# TPS54331_Neko_BEC.net
KiCad netlist of a schematic drawn in EasyEDA Pro
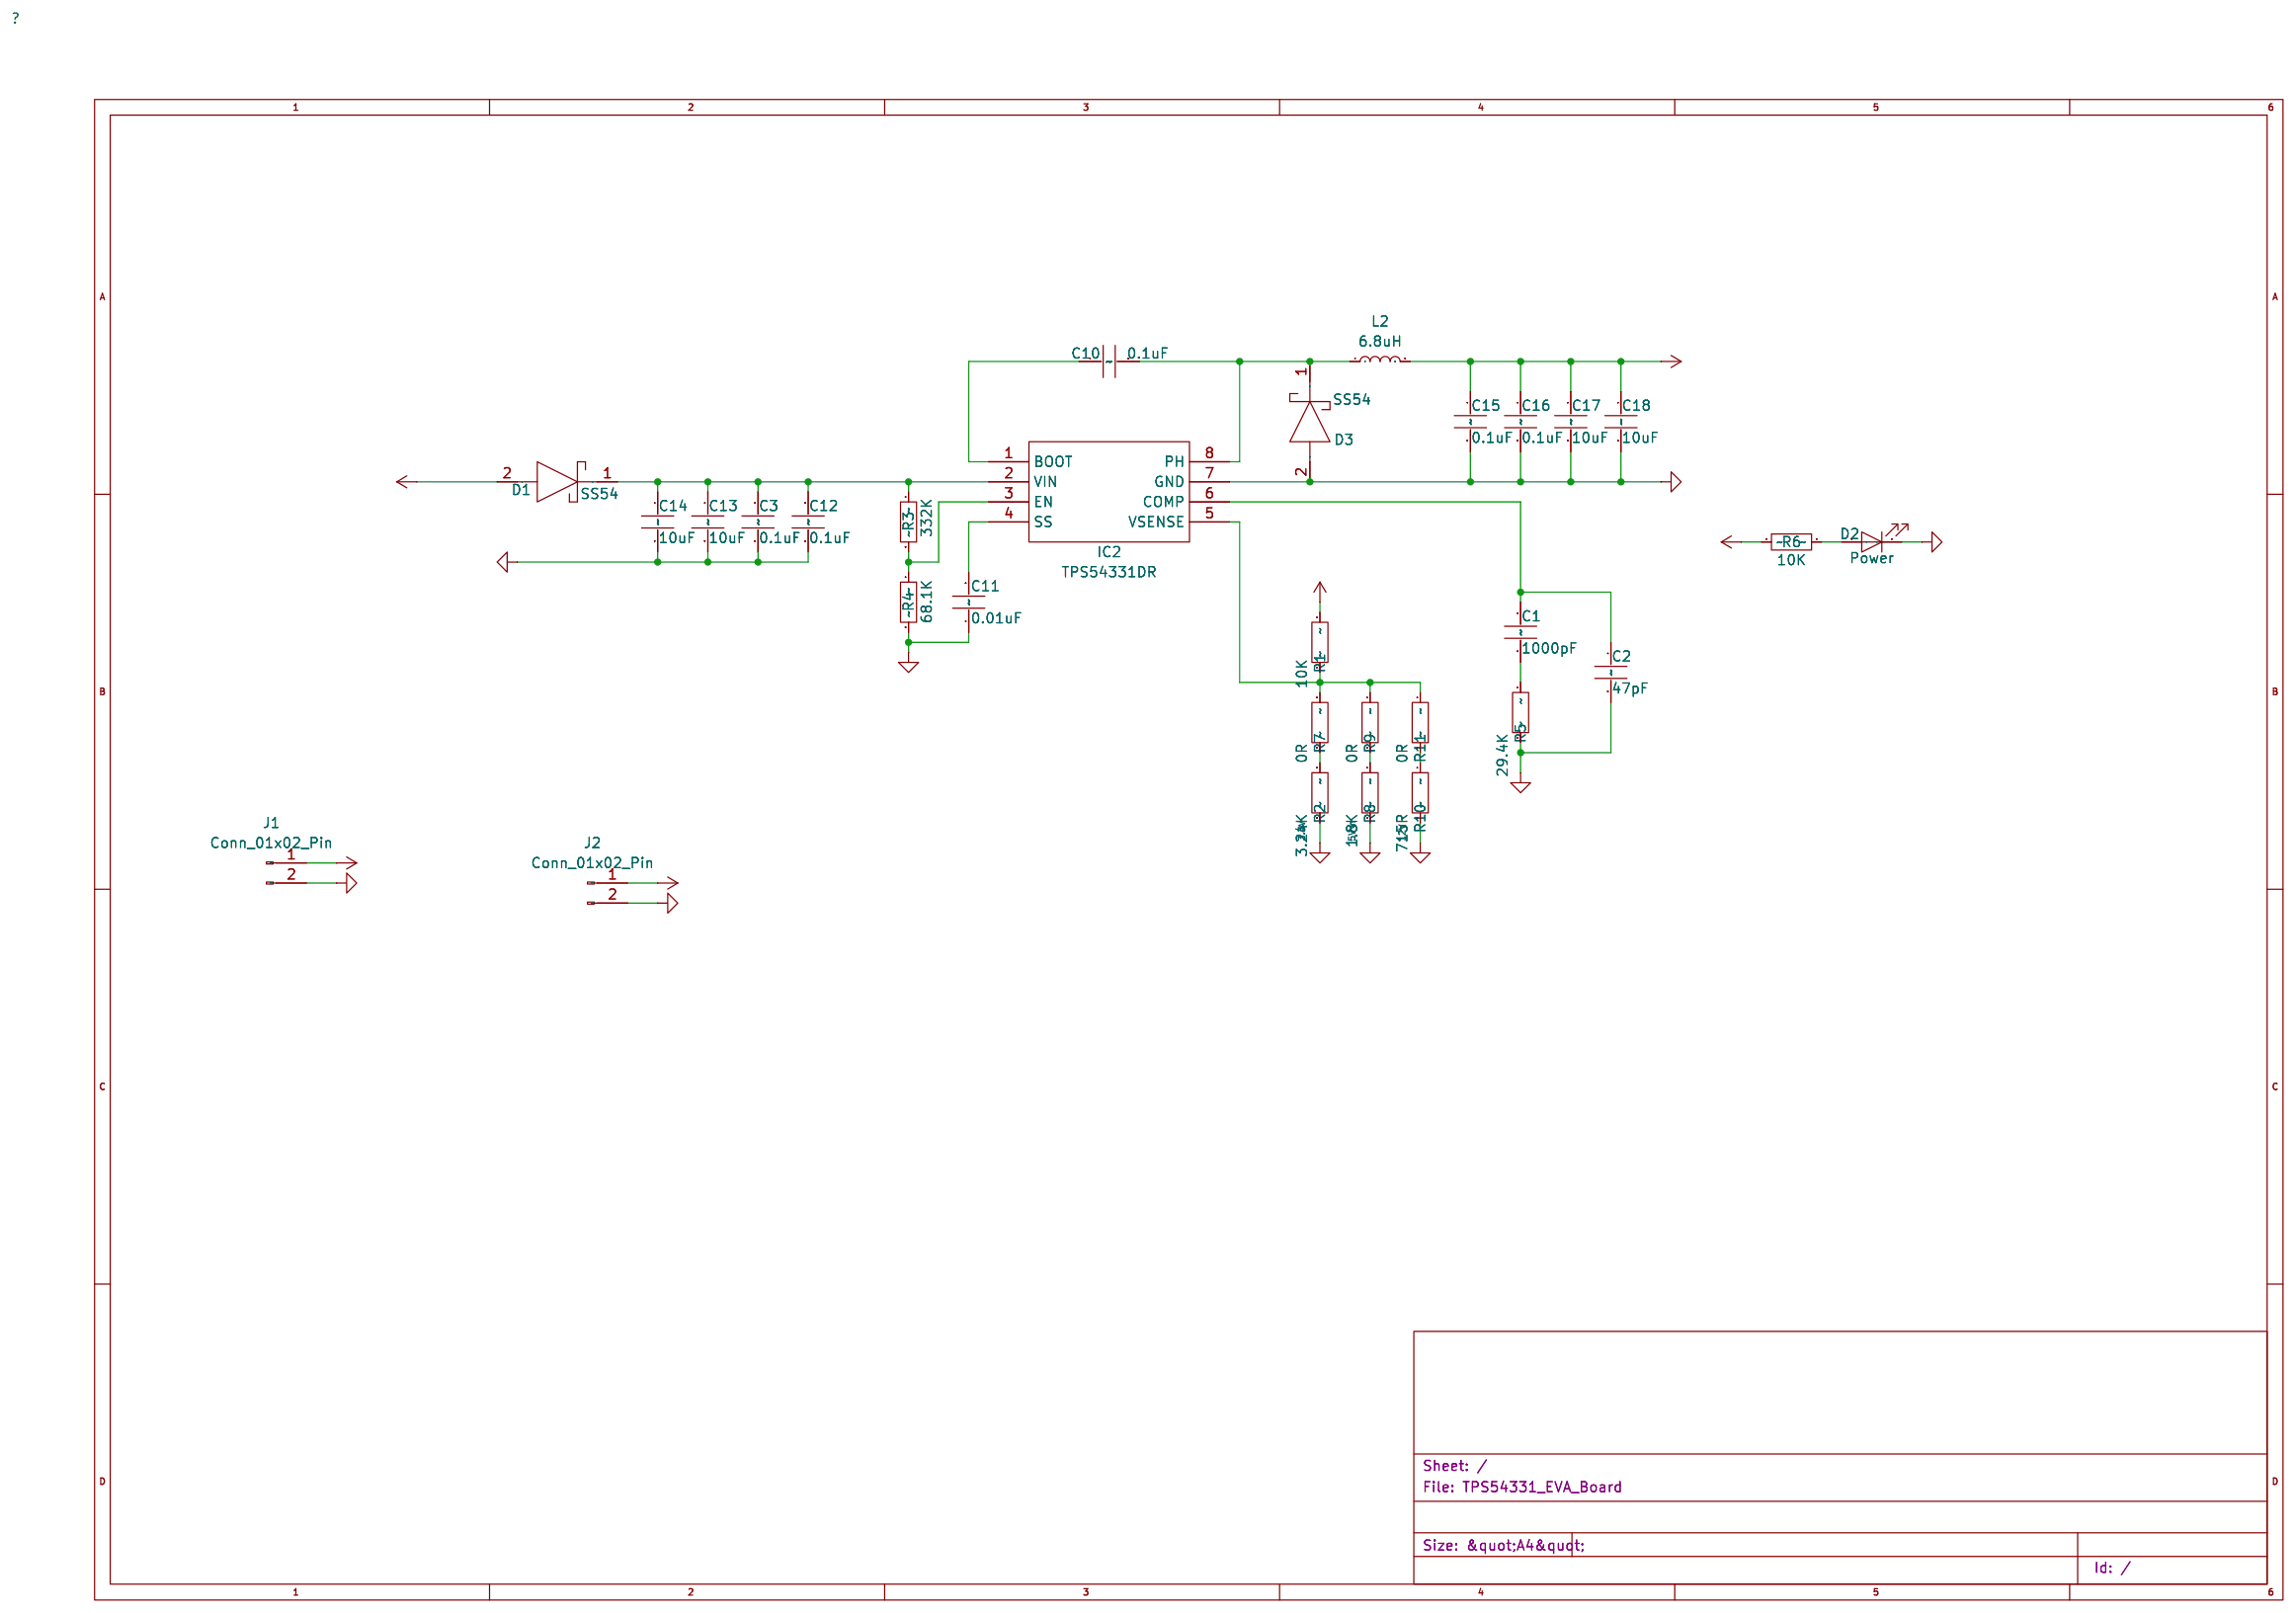
[diagram p0: schematic sheet]

(export (version "E")
  (design (tool "Eeschema 10.0.6"))
  (components
    (comp (ref "C1")
      (value "1000pF")
      (footprint "easyedapro:Capacitor_SMD:C_1206_3216Metric")
      (description "Unpolarized capacitor")
      (libsource (lib "easyedapro") (part "Device_C"))
    )
    (comp (ref "C2")
      (value "47pF")
      (footprint "easyedapro:Capacitor_SMD:C_1206_3216Metric")
      (description "Unpolarized capacitor")
      (libsource (lib "easyedapro") (part "Device_C"))
    )
    (comp (ref "C3")
      (value "0.1uF")
      (footprint "easyedapro:Capacitor_SMD:C_1206_3216Metric")
      (description "Unpolarized capacitor")
      (libsource (lib "easyedapro") (part "Device_C"))
    )
    (comp (ref "C10")
      (value "0.1uF")
      (footprint "easyedapro:Capacitor_SMD:C_1206_3216Metric")
      (description "Unpolarized capacitor")
      (libsource (lib "easyedapro") (part "Device_C"))
    )
    (comp (ref "C11")
      (value "0.01uF")
      (footprint "easyedapro:Capacitor_SMD:C_1206_3216Metric")
      (description "Unpolarized capacitor")
      (libsource (lib "easyedapro") (part "Device_C"))
    )
    (comp (ref "C12")
      (value "0.1uF")
      (footprint "easyedapro:Capacitor_SMD:C_1206_3216Metric")
      (description "Unpolarized capacitor")
      (libsource (lib "easyedapro") (part "Device_C"))
    )
    (comp (ref "C13")
      (value "10uF")
      (footprint "easyedapro:Capacitor_SMD:C_1206_3216Metric")
      (description "Unpolarized capacitor")
      (libsource (lib "easyedapro") (part "Device_C"))
    )
    (comp (ref "C14")
      (value "10uF")
      (footprint "easyedapro:Capacitor_SMD:C_1206_3216Metric")
      (description "Unpolarized capacitor")
      (libsource (lib "easyedapro") (part "Device_C"))
    )
    (comp (ref "C15")
      (value "0.1uF")
      (footprint "easyedapro:Capacitor_SMD:C_1206_3216Metric")
      (description "Unpolarized capacitor")
      (libsource (lib "easyedapro") (part "Device_C"))
    )
    (comp (ref "C16")
      (value "0.1uF")
      (footprint "easyedapro:Capacitor_SMD:C_1206_3216Metric")
      (description "Unpolarized capacitor")
      (libsource (lib "easyedapro") (part "Device_C"))
    )
    (comp (ref "C17")
      (value "10uF")
      (footprint "easyedapro:Capacitor_SMD:C_1206_3216Metric")
      (description "Unpolarized capacitor")
      (libsource (lib "easyedapro") (part "Device_C"))
    )
    (comp (ref "C18")
      (value "10uF")
      (footprint "easyedapro:Capacitor_SMD:C_1206_3216Metric")
      (description "Unpolarized capacitor")
      (libsource (lib "easyedapro") (part "Device_C"))
    )
    (comp (ref "D1")
      (value "SS54")
      (footprint "easyedapro:SamacSys_Parts:DIOM5126X245N")
      (description "40V 550mV@5A 5A SMA(DO-214AC) Schottky Barrier Diodes (SBD)")
      (libsource (lib "easyedapro") (part "SamacSys_Parts_SS54"))
    )
    (comp (ref "D2")
      (value "Power")
      (footprint "easyedapro:LED_SMD:LED_0603_1608Metric")
      (description "Light emitting diode")
      (libsource (lib "easyedapro") (part "Device_LED"))
    )
    (comp (ref "D3")
      (value "SS54")
      (footprint "easyedapro:SamacSys_Parts:DIOM5126X245N")
      (description "40V 550mV@5A 5A SMA(DO-214AC) Schottky Barrier Diodes (SBD)")
      (libsource (lib "easyedapro") (part "SamacSys_Parts_SS54"))
    )
    (comp (ref "IC2")
      (value "TPS54331DR")
      (footprint "easyedapro:SamacSys_Parts:SOIC127P600X175-8N")
      (description "Texas Instruments TPS54331DR, Step Down DC-DC Converter, 3A, Adjustable, 0.8  25 V, 8-Pin SOIC")
      (fields (field (name "Mouser Part Number") "595-TPS54331DR"))
      (libsource (lib "easyedapro") (part "SamacSys_Parts_TPS54331DR"))
    )
    (comp (ref "J1")
      (value "Conn_01x02_Pin")
      (footprint "easyedapro:SamacSys_Parts:Power_PAD")
      (description "Generic connector, single row, 01x02, script generated")
      (libsource (lib "easyedapro") (part "Connector_Conn_01x02_Pin"))
    )
    (comp (ref "J2")
      (value "Conn_01x02_Pin")
      (footprint "easyedapro:SamacSys_Parts:Power_PAD")
      (description "Generic connector, single row, 01x02, script generated")
      (libsource (lib "easyedapro") (part "Connector_Conn_01x02_Pin"))
    )
    (comp (ref "L2")
      (value "6.8uH")
      (footprint "easyedapro:Inductor_SMD:L_Changjiang_FNR5040S")
      (description "Inductor")
      (libsource (lib "easyedapro") (part "Device_L"))
    )
    (comp (ref "R1")
      (value "10K")
      (footprint "easyedapro:Resistor_SMD:R_0603_1608Metric")
      (description "Resistor")
      (libsource (lib "easyedapro") (part "Device_R"))
    )
    (comp (ref "R2")
      (value "3.24K")
      (footprint "easyedapro:Resistor_SMD:R_0603_1608Metric")
      (description "Resistor")
      (libsource (lib "easyedapro") (part "Device_R"))
    )
    (comp (ref "R3")
      (value "332K")
      (footprint "easyedapro:Resistor_SMD:R_0603_1608Metric")
      (description "Resistor")
      (libsource (lib "easyedapro") (part "Device_R"))
    )
    (comp (ref "R4")
      (value "68.1K")
      (footprint "easyedapro:Resistor_SMD:R_0603_1608Metric")
      (description "Resistor")
      (libsource (lib "easyedapro") (part "Device_R"))
    )
    (comp (ref "R5")
      (value "29.4K")
      (footprint "easyedapro:Resistor_SMD:R_0603_1608Metric")
      (description "Resistor")
      (libsource (lib "easyedapro") (part "Device_R"))
    )
    (comp (ref "R6")
      (value "10K")
      (footprint "easyedapro:Resistor_SMD:R_0603_1608Metric")
      (description "Resistor")
      (libsource (lib "easyedapro") (part "Device_R"))
    )
    (comp (ref "R7")
      (value "0R")
      (footprint "easyedapro:Resistor_SMD:R_0603_1608Metric")
      (description "Resistor")
      (libsource (lib "easyedapro") (part "Device_R"))
    )
    (comp (ref "R8")
      (value "1.8K")
      (footprint "easyedapro:Resistor_SMD:R_0603_1608Metric")
      (description "Resistor")
      (libsource (lib "easyedapro") (part "Device_R"))
    )
    (comp (ref "R9")
      (value "0R")
      (footprint "easyedapro:Resistor_SMD:R_0603_1608Metric")
      (description "Resistor")
      (libsource (lib "easyedapro") (part "Device_R"))
    )
    (comp (ref "R10")
      (value "715R")
      (footprint "easyedapro:Resistor_SMD:R_0603_1608Metric")
      (description "Resistor")
      (libsource (lib "easyedapro") (part "Device_R"))
    )
    (comp (ref "R11")
      (value "0R")
      (footprint "easyedapro:Resistor_SMD:R_0603_1608Metric")
      (description "Resistor")
      (libsource (lib "easyedapro") (part "Device_R"))
    )
  )
  (nets
    (net (code "1") (name "Net-(C1-~-Pad2)") (class "Default")
      (node (ref "C1") (pin "2") (pinfunction "~_2") (pintype "unspecified"))
      (node (ref "R5") (pin "1") (pinfunction "~_1") (pintype "unspecified"))
    )
    (net (code "2") (name "Net-(D1-K)") (class "Default")
      (node (ref "C12") (pin "1") (pinfunction "~_1") (pintype "unspecified"))
      (node (ref "C13") (pin "1") (pinfunction "~_1") (pintype "unspecified"))
      (node (ref "C14") (pin "1") (pinfunction "~_1") (pintype "unspecified"))
      (node (ref "C3") (pin "1") (pinfunction "~_1") (pintype "unspecified"))
      (node (ref "D1") (pin "1") (pinfunction "K_1") (pintype "unspecified"))
      (node (ref "IC2") (pin "2") (pinfunction "VIN_2") (pintype "unspecified"))
      (node (ref "R3") (pin "1") (pinfunction "~_1") (pintype "unspecified"))
    )
    (net (code "3") (name "Net-(D2-A)") (class "Default")
      (node (ref "D2") (pin "2") (pinfunction "A_2") (pintype "unspecified"))
      (node (ref "R6") (pin "2") (pinfunction "~_2") (pintype "unspecified"))
    )
    (net (code "4") (name "Net-(D3-K)") (class "Default")
      (node (ref "C10") (pin "2") (pinfunction "~_2") (pintype "unspecified"))
      (node (ref "D3") (pin "1") (pinfunction "K_1") (pintype "unspecified"))
      (node (ref "IC2") (pin "8") (pinfunction "PH_8") (pintype "unspecified"))
      (node (ref "L2") (pin "1") (pinfunction "1_1") (pintype "unspecified"))
    )
    (net (code "5") (name "Net-(IC2-BOOT)") (class "Default")
      (node (ref "C10") (pin "1") (pinfunction "~_1") (pintype "unspecified"))
      (node (ref "IC2") (pin "1") (pinfunction "BOOT_1") (pintype "unspecified"))
    )
    (net (code "6") (name "Net-(IC2-COMP)") (class "Default")
      (node (ref "C1") (pin "1") (pinfunction "~_1") (pintype "unspecified"))
      (node (ref "C2") (pin "1") (pinfunction "~_1") (pintype "unspecified"))
      (node (ref "IC2") (pin "6") (pinfunction "COMP_6") (pintype "unspecified"))
    )
    (net (code "7") (name "Net-(IC2-EN)") (class "Default")
      (node (ref "IC2") (pin "3") (pinfunction "EN_3") (pintype "unspecified"))
      (node (ref "R3") (pin "2") (pinfunction "~_2") (pintype "unspecified"))
      (node (ref "R4") (pin "1") (pinfunction "~_1") (pintype "unspecified"))
    )
    (net (code "8") (name "Net-(IC2-SS)") (class "Default")
      (node (ref "C11") (pin "2") (pinfunction "~_2") (pintype "unspecified"))
      (node (ref "IC2") (pin "4") (pinfunction "SS_4") (pintype "unspecified"))
    )
    (net (code "9") (name "Net-(IC2-VSENSE)") (class "Default")
      (node (ref "IC2") (pin "5") (pinfunction "VSENSE_5") (pintype "unspecified"))
      (node (ref "R1") (pin "2") (pinfunction "~_2") (pintype "unspecified"))
      (node (ref "R11") (pin "1") (pinfunction "~_1") (pintype "unspecified"))
      (node (ref "R7") (pin "1") (pinfunction "~_1") (pintype "unspecified"))
      (node (ref "R9") (pin "1") (pinfunction "~_1") (pintype "unspecified"))
    )
    (net (code "10") (name "Net-(R2-~-Pad1)") (class "Default")
      (node (ref "R2") (pin "1") (pinfunction "~_1") (pintype "unspecified"))
      (node (ref "R7") (pin "2") (pinfunction "~_2") (pintype "unspecified"))
    )
    (net (code "11") (name "Net-(R8-~-Pad1)") (class "Default")
      (node (ref "R8") (pin "1") (pinfunction "~_1") (pintype "unspecified"))
      (node (ref "R9") (pin "2") (pinfunction "~_2") (pintype "unspecified"))
    )
    (net (code "12") (name "Net-(R10-~-Pad1)") (class "Default")
      (node (ref "R10") (pin "1") (pinfunction "~_1") (pintype "unspecified"))
      (node (ref "R11") (pin "2") (pinfunction "~_2") (pintype "unspecified"))
    )
    (net (code "13") (name "POWER_+5V") (class "Default")
      (node (ref "C15") (pin "1") (pinfunction "~_1") (pintype "unspecified"))
      (node (ref "C16") (pin "1") (pinfunction "~_1") (pintype "unspecified"))
      (node (ref "C17") (pin "1") (pinfunction "~_1") (pintype "unspecified"))
      (node (ref "C18") (pin "1") (pinfunction "~_1") (pintype "unspecified"))
      (node (ref "J2") (pin "1") (pinfunction "Pin_1_1") (pintype "unspecified"))
      (node (ref "L2") (pin "2") (pinfunction "2_2") (pintype "unspecified"))
      (node (ref "R1") (pin "1") (pinfunction "~_1") (pintype "unspecified"))
      (node (ref "R6") (pin "1") (pinfunction "~_1") (pintype "unspecified"))
    )
    (net (code "14") (name "POWER_GND") (class "Default")
      (node (ref "C11") (pin "1") (pinfunction "~_1") (pintype "unspecified"))
      (node (ref "C12") (pin "2") (pinfunction "~_2") (pintype "unspecified"))
      (node (ref "C13") (pin "2") (pinfunction "~_2") (pintype "unspecified"))
      (node (ref "C14") (pin "2") (pinfunction "~_2") (pintype "unspecified"))
      (node (ref "C15") (pin "2") (pinfunction "~_2") (pintype "unspecified"))
      (node (ref "C16") (pin "2") (pinfunction "~_2") (pintype "unspecified"))
      (node (ref "C17") (pin "2") (pinfunction "~_2") (pintype "unspecified"))
      (node (ref "C18") (pin "2") (pinfunction "~_2") (pintype "unspecified"))
      (node (ref "C2") (pin "2") (pinfunction "~_2") (pintype "unspecified"))
      (node (ref "C3") (pin "2") (pinfunction "~_2") (pintype "unspecified"))
      (node (ref "D2") (pin "1") (pinfunction "K_1") (pintype "unspecified"))
      (node (ref "D3") (pin "2") (pinfunction "A_2") (pintype "unspecified"))
      (node (ref "IC2") (pin "7") (pinfunction "GND_7") (pintype "unspecified"))
      (node (ref "J1") (pin "2") (pinfunction "Pin_2_2") (pintype "unspecified"))
      (node (ref "J2") (pin "2") (pinfunction "Pin_2_2") (pintype "unspecified"))
      (node (ref "R10") (pin "2") (pinfunction "~_2") (pintype "unspecified"))
      (node (ref "R2") (pin "2") (pinfunction "~_2") (pintype "unspecified"))
      (node (ref "R4") (pin "2") (pinfunction "~_2") (pintype "unspecified"))
      (node (ref "R5") (pin "2") (pinfunction "~_2") (pintype "unspecified"))
      (node (ref "R8") (pin "2") (pinfunction "~_2") (pintype "unspecified"))
    )
    (net (code "15") (name "POWER_VCC") (class "Default")
      (node (ref "D1") (pin "2") (pinfunction "A_2") (pintype "unspecified"))
      (node (ref "J1") (pin "1") (pinfunction "Pin_1_1") (pintype "unspecified"))
    )
  )
)
